# IM828XCC.net
KiCad netlist of a schematic drawn in Altium Designer
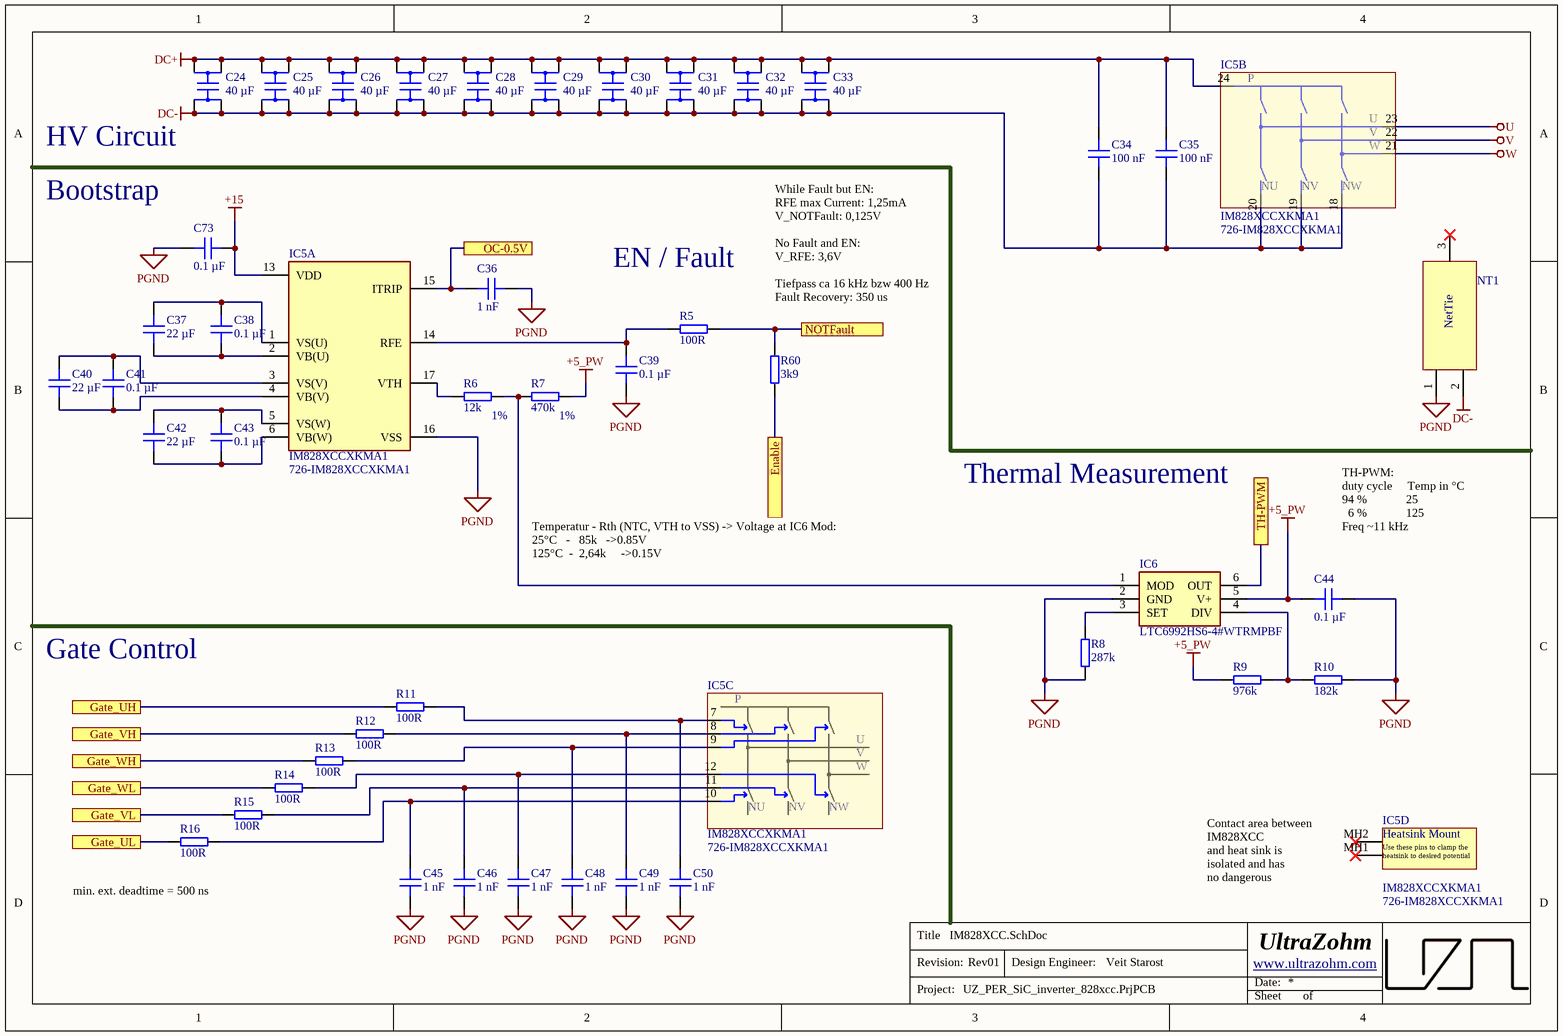
[diagram p0: IM828XCC.SchDoc]

(export (version "E")
  (design (tool "Eeschema 10.0.6"))
  (components
    (comp (ref "C24")
      (value "40 µF")
      (footprint "B32778Z")
      (description "Film Capacitors, 40 µF, 1000 VDC for DC Link")
      (fields
        (field (name "MANUFACTURER PART NUMBER") "B32778Z0406K000")
        (field (name "MANUFACTURER") "EPCOS / TDK")
        (field (name "CREATED FROM") "VStarost")
      )
      (libsource (lib "") (part "Capacitor_1"))
    )
    (comp (ref "C25")
      (value "40 µF")
      (footprint "B32778Z")
      (description "Film Capacitors, 40 µF, 1000 VDC for DC Link")
      (fields
        (field (name "MANUFACTURER PART NUMBER") "B32778Z0406K000")
        (field (name "MANUFACTURER") "EPCOS / TDK")
        (field (name "CREATED FROM") "VStarost")
      )
      (libsource (lib "") (part "Capacitor_1"))
    )
    (comp (ref "C26")
      (value "40 µF")
      (footprint "B32778Z")
      (description "Film Capacitors, 40 µF, 1000 VDC for DC Link")
      (fields
        (field (name "MANUFACTURER PART NUMBER") "B32778Z0406K000")
        (field (name "MANUFACTURER") "EPCOS / TDK")
        (field (name "CREATED FROM") "VStarost")
      )
      (libsource (lib "") (part "Capacitor_1"))
    )
    (comp (ref "C27")
      (value "40 µF")
      (footprint "B32778Z")
      (description "Film Capacitors, 40 µF, 1000 VDC for DC Link")
      (fields
        (field (name "MANUFACTURER PART NUMBER") "B32778Z0406K000")
        (field (name "MANUFACTURER") "EPCOS / TDK")
        (field (name "CREATED FROM") "VStarost")
      )
      (libsource (lib "") (part "Capacitor_1"))
    )
    (comp (ref "C28")
      (value "40 µF")
      (footprint "B32778Z")
      (description "Film Capacitors, 40 µF, 1000 VDC for DC Link")
      (fields
        (field (name "MANUFACTURER PART NUMBER") "B32778Z0406K000")
        (field (name "MANUFACTURER") "EPCOS / TDK")
        (field (name "CREATED FROM") "VStarost")
      )
      (libsource (lib "") (part "Capacitor_1"))
    )
    (comp (ref "C29")
      (value "40 µF")
      (footprint "B32778Z")
      (description "Film Capacitors, 40 µF, 1000 VDC for DC Link")
      (fields
        (field (name "MANUFACTURER PART NUMBER") "B32778Z0406K000")
        (field (name "MANUFACTURER") "EPCOS / TDK")
        (field (name "CREATED FROM") "VStarost")
      )
      (libsource (lib "") (part "Capacitor_1"))
    )
    (comp (ref "C30")
      (value "40 µF")
      (footprint "B32778Z")
      (description "Film Capacitors, 40 µF, 1000 VDC for DC Link")
      (fields
        (field (name "MANUFACTURER PART NUMBER") "B32778Z0406K000")
        (field (name "MANUFACTURER") "EPCOS / TDK")
        (field (name "CREATED FROM") "VStarost")
      )
      (libsource (lib "") (part "Capacitor_1"))
    )
    (comp (ref "C31")
      (value "40 µF")
      (footprint "B32778Z")
      (description "Film Capacitors, 40 µF, 1000 VDC for DC Link")
      (fields
        (field (name "MANUFACTURER PART NUMBER") "B32778Z0406K000")
        (field (name "MANUFACTURER") "EPCOS / TDK")
        (field (name "CREATED FROM") "VStarost")
      )
      (libsource (lib "") (part "Capacitor_1"))
    )
    (comp (ref "C32")
      (value "40 µF")
      (footprint "B32778Z")
      (description "Film Capacitors, 40 µF, 1000 VDC for DC Link")
      (fields
        (field (name "MANUFACTURER PART NUMBER") "B32778Z0406K000")
        (field (name "MANUFACTURER") "EPCOS / TDK")
        (field (name "CREATED FROM") "VStarost")
      )
      (libsource (lib "") (part "Capacitor_1"))
    )
    (comp (ref "C33")
      (value "40 µF")
      (footprint "B32778Z")
      (description "Film Capacitors, 40 µF, 1000 VDC for DC Link")
      (fields
        (field (name "MANUFACTURER PART NUMBER") "B32778Z0406K000")
        (field (name "MANUFACTURER") "EPCOS / TDK")
        (field (name "CREATED FROM") "VStarost")
      )
      (libsource (lib "") (part "Capacitor_1"))
    )
    (comp (ref "C34")
      (value "100 nF")
      (footprint "WIMA")
      (description "Folienkondensatoren 1600V .10uF 10% PCM 27.5")
      (fields
        (field (name "MANUFACTURER PART NUMBER") "MKP1T031006B00KYSD")
        (field (name "MANUFACTURER") "WIMA")
        (field (name "CREATED FROM") "VStarost")
      )
      (libsource (lib "user") (part "Capacitor"))
    )
    (comp (ref "C35")
      (value "100 nF")
      (footprint "WIMA")
      (description "Folienkondensatoren 1600V .10uF 10% PCM 27.5")
      (fields
        (field (name "MANUFACTURER PART NUMBER") "MKP1T031006B00KYSD")
        (field (name "MANUFACTURER") "WIMA")
        (field (name "CREATED FROM") "VStarost")
      )
      (libsource (lib "user") (part "Capacitor"))
    )
    (comp (ref "C36")
      (value "1 nF")
      (footprint "C_0603")
      (description "Capacitor 0603, 50 VDC, 1 nF, C0G")
      (fields
        (field (name "MANUFACTURER PART NUMBER") "06035A102JAT2A")
        (field (name "MANUFACTURER") "AVX")
        (field (name "CREATED FROM") "MGremer")
      )
      (libsource (lib "user") (part "Capacitor"))
    )
    (comp (ref "C37")
      (value "22 µF")
      (footprint "C_1206")
      (description "Capacitor 1206, 35 VDC, 22µF, X5R")
      (fields
        (field (name "MANUFACTURER PART NUMBER") "C3216X5R1V226M160AC")
        (field (name "MANUFACTURER") "TDK")
        (field (name "CREATED FROM") "VStarost")
      )
      (libsource (lib "user") (part "Capacitor"))
    )
    (comp (ref "C38")
      (value "0.1 µF")
      (footprint "C_0603")
      (description "Capacitor 0603, 50 VDC, 0.1 µF, X7R")
      (fields
        (field (name "MANUFACTURER PART NUMBER") "C0603X104K5RAC7411")
        (field (name "MANUFACTURER") "KEMET")
        (field (name "CREATED FROM") "MGremer")
      )
      (libsource (lib "user") (part "Capacitor"))
    )
    (comp (ref "C39")
      (value "0.1 µF")
      (footprint "C_0603")
      (description "Capacitor 0603, 50 VDC, 0.1 µF, X7R")
      (fields
        (field (name "MANUFACTURER PART NUMBER") "C0603X104K5RAC7411")
        (field (name "MANUFACTURER") "KEMET")
        (field (name "CREATED FROM") "MGremer")
      )
      (libsource (lib "user") (part "Capacitor"))
    )
    (comp (ref "C40")
      (value "22 µF")
      (footprint "C_1206")
      (description "Capacitor 1206, 35 VDC, 22µF, X5R")
      (fields
        (field (name "MANUFACTURER PART NUMBER") "C3216X5R1V226M160AC")
        (field (name "MANUFACTURER") "TDK")
        (field (name "CREATED FROM") "VStarost")
      )
      (libsource (lib "user") (part "Capacitor"))
    )
    (comp (ref "C41")
      (value "0.1 µF")
      (footprint "C_0603")
      (description "Capacitor 0603, 50 VDC, 0.1 µF, X7R")
      (fields
        (field (name "MANUFACTURER PART NUMBER") "C0603X104K5RAC7411")
        (field (name "MANUFACTURER") "KEMET")
        (field (name "CREATED FROM") "MGremer")
      )
      (libsource (lib "user") (part "Capacitor"))
    )
    (comp (ref "C42")
      (value "22 µF")
      (footprint "C_1206")
      (description "Capacitor 1206, 35 VDC, 22µF, X5R")
      (fields
        (field (name "MANUFACTURER PART NUMBER") "C3216X5R1V226M160AC")
        (field (name "MANUFACTURER") "TDK")
        (field (name "CREATED FROM") "VStarost")
      )
      (libsource (lib "user") (part "Capacitor"))
    )
    (comp (ref "C43")
      (value "0.1 µF")
      (footprint "C_0603")
      (description "Capacitor 0603, 50 VDC, 0.1 µF, X7R")
      (fields
        (field (name "MANUFACTURER PART NUMBER") "C0603X104K5RAC7411")
        (field (name "MANUFACTURER") "KEMET")
        (field (name "CREATED FROM") "MGremer")
      )
      (libsource (lib "user") (part "Capacitor"))
    )
    (comp (ref "C44")
      (value "0.1 µF")
      (footprint "C_0603")
      (description "Capacitor 0603, 50 VDC, 0.1 µF, X7R")
      (fields
        (field (name "MANUFACTURER PART NUMBER") "C0603X104K5RAC7411")
        (field (name "MANUFACTURER") "KEMET")
        (field (name "CREATED FROM") "MGremer")
      )
      (libsource (lib "user") (part "Capacitor"))
    )
    (comp (ref "C45")
      (value "1 nF")
      (footprint "C_0603")
      (description "Capacitor 0603, 50 VDC, 1 nF, C0G")
      (fields
        (field (name "MANUFACTURER PART NUMBER") "06035A102JAT2A")
        (field (name "MANUFACTURER") "AVX")
        (field (name "CREATED FROM") "MGremer")
      )
      (libsource (lib "user") (part "Capacitor"))
    )
    (comp (ref "C46")
      (value "1 nF")
      (footprint "C_0603")
      (description "Capacitor 0603, 50 VDC, 1 nF, C0G")
      (fields
        (field (name "MANUFACTURER PART NUMBER") "06035A102JAT2A")
        (field (name "MANUFACTURER") "AVX")
        (field (name "CREATED FROM") "MGremer")
      )
      (libsource (lib "user") (part "Capacitor"))
    )
    (comp (ref "C47")
      (value "1 nF")
      (footprint "C_0603")
      (description "Capacitor 0603, 50 VDC, 1 nF, C0G")
      (fields
        (field (name "MANUFACTURER PART NUMBER") "06035A102JAT2A")
        (field (name "MANUFACTURER") "AVX")
        (field (name "CREATED FROM") "MGremer")
      )
      (libsource (lib "user") (part "Capacitor"))
    )
    (comp (ref "C48")
      (value "1 nF")
      (footprint "C_0603")
      (description "Capacitor 0603, 50 VDC, 1 nF, C0G")
      (fields
        (field (name "MANUFACTURER PART NUMBER") "06035A102JAT2A")
        (field (name "MANUFACTURER") "AVX")
        (field (name "CREATED FROM") "MGremer")
      )
      (libsource (lib "user") (part "Capacitor"))
    )
    (comp (ref "C49")
      (value "1 nF")
      (footprint "C_0603")
      (description "Capacitor 0603, 50 VDC, 1 nF, C0G")
      (fields
        (field (name "MANUFACTURER PART NUMBER") "06035A102JAT2A")
        (field (name "MANUFACTURER") "AVX")
        (field (name "CREATED FROM") "MGremer")
      )
      (libsource (lib "user") (part "Capacitor"))
    )
    (comp (ref "C50")
      (value "1 nF")
      (footprint "C_0603")
      (description "Capacitor 0603, 50 VDC, 1 nF, C0G")
      (fields
        (field (name "MANUFACTURER PART NUMBER") "06035A102JAT2A")
        (field (name "MANUFACTURER") "AVX")
        (field (name "CREATED FROM") "MGremer")
      )
      (libsource (lib "user") (part "Capacitor"))
    )
    (comp (ref "C73")
      (value "0.1 µF")
      (footprint "C_0603")
      (description "Capacitor 0603, 50 VDC, 0.1 µF, X7R")
      (fields
        (field (name "MANUFACTURER PART NUMBER") "C0603X104K5RAC7411")
        (field (name "MANUFACTURER") "KEMET")
        (field (name "CREATED FROM") "MGremer")
      )
      (libsource (lib "user") (part "Capacitor"))
    )
    (comp (ref "IC5")
      (value "IM828XCCXKMA1")
      (footprint "IM828XCCXKMA1")
      (description "Motor/Motion/Ignition Controllers & Drivers SiC MOSFET")
      (fields
        (field (name "MOUSER PART NUMBER") "726-IM828XCCXKMA1")
        (field (name "SUPPLIER PART NUMBER 1") "726-IM828XCCXKMA1")
        (field (name "MANUFACTURER") "Infineon")
        (field (name "CREATED FROM") "VStarost")
      )
      (libsource (lib "user") (part "IM828XCCXKMA1"))
    )
    (comp (ref "IC6")
      (value "LTC6992HS6-4#WTRMPBF")
      (footprint "SOT95P280X100-6N")
      (description "Switching Controllers PWM with 5% to 100% Pulse Width Control")
      (fields (field (name "MANUFACTURER") "Analog Devices") (field (name "CREATED FROM") "DHufnagel"))
      (libsource (lib "user") (part "LTC6992HS6-4#WTRMPBF"))
    )
    (comp (ref "NT1")
      (value "Net Tie 2 to 1")
      (footprint "2_to_1_NetTie_1mm")
      (description "Net Tie 2 to 1. Joints two nets without producing a DRC error")
      (fields (field (name "CREATED BY") "T. Wendt"))
      (libsource (lib "user") (part "NetTie_2_to_1"))
    )
    (comp (ref "R5")
      (value "100R")
      (footprint "RES 0603_1608")
      (description "SMD resistor E24 series")
      (fields
        (field (name "MANUFACTURER PART NUMBER") "RK73B1JTTD101J")
        (field (name "MANUFACTURER") "KOA Speer")
        (field (name "CREATED FROM") "MGremer")
      )
      (libsource (lib "user") (part "Resistor"))
    )
    (comp (ref "R6")
      (value "12k")
      (footprint "RES 0603_1608")
      (description "SMD resistor E24 series 12 kOhms 100mW 0603 1%")
      (fields
        (field (name "MANUFACTURER PART NUMBER") "AC0603FR-1012KL")
        (field (name "MANUFACTURER") "YAGEO")
        (field (name "TOLERANCE") "1%")
        (field (name "CREATED FROM") "VStarost")
      )
      (libsource (lib "user") (part "Resistor"))
    )
    (comp (ref "R7")
      (value "470k")
      (footprint "RES 0603_1608")
      (description "SMD resistor E24 series 470 kOhms 100-200 mW 0603 1%")
      (fields
        (field (name "MANUFACTURER PART NUMBER") "RC0603FR-10470KL")
        (field (name "MANUFACTURER") "YAGEO")
        (field (name "TOLERANCE") "1%")
        (field (name "CREATED FROM") "VStarost")
      )
      (libsource (lib "user") (part "Resistor"))
    )
    (comp (ref "R8")
      (value "287k")
      (footprint "RES 0805_2012")
      (description "SMD resistor 1%")
      (fields
        (field (name "MANUFACTURER PART NUMBER") "ERJ-6ENF2873V")
        (field (name "MANUFACTURER") "Panasonic")
        (field (name "CREATED FROM") "MGremer")
      )
      (libsource (lib "user") (part "Resistor"))
    )
    (comp (ref "R9")
      (value "976k")
      (footprint "RES 0603_1608")
      (description "SMD resistor 1%, 50V, 100ppm")
      (fields
        (field (name "MANUFACTURER PART NUMBER") "CR0603-FX-9763ELF")
        (field (name "MANUFACTURER") "Bourns")
        (field (name "CREATED FROM") "DHufnagel")
      )
      (libsource (lib "user") (part "Resistor"))
    )
    (comp (ref "R10")
      (value "182k")
      (footprint "RES 0603_1608")
      (description "SMD resistor 1%, 50V, 100ppm")
      (fields
        (field (name "MANUFACTURER PART NUMBER") "CR0603-FX-1823ELF")
        (field (name "MANUFACTURER") "Bourns")
        (field (name "CREATED FROM") "DHufnagel")
      )
      (libsource (lib "user") (part "Resistor"))
    )
    (comp (ref "R11")
      (value "100R")
      (footprint "RES 0603_1608")
      (description "SMD resistor E24 series")
      (fields
        (field (name "MANUFACTURER PART NUMBER") "RK73B1JTTD101J")
        (field (name "MANUFACTURER") "KOA Speer")
        (field (name "CREATED FROM") "MGremer")
      )
      (libsource (lib "user") (part "Resistor"))
    )
    (comp (ref "R12")
      (value "100R")
      (footprint "RES 0603_1608")
      (description "SMD resistor E24 series")
      (fields
        (field (name "MANUFACTURER PART NUMBER") "RK73B1JTTD101J")
        (field (name "MANUFACTURER") "KOA Speer")
        (field (name "CREATED FROM") "MGremer")
      )
      (libsource (lib "user") (part "Resistor"))
    )
    (comp (ref "R13")
      (value "100R")
      (footprint "RES 0603_1608")
      (description "SMD resistor E24 series")
      (fields
        (field (name "MANUFACTURER PART NUMBER") "RK73B1JTTD101J")
        (field (name "MANUFACTURER") "KOA Speer")
        (field (name "CREATED FROM") "MGremer")
      )
      (libsource (lib "user") (part "Resistor"))
    )
    (comp (ref "R14")
      (value "100R")
      (footprint "RES 0603_1608")
      (description "SMD resistor E24 series")
      (fields
        (field (name "MANUFACTURER PART NUMBER") "RK73B1JTTD101J")
        (field (name "MANUFACTURER") "KOA Speer")
        (field (name "CREATED FROM") "MGremer")
      )
      (libsource (lib "user") (part "Resistor"))
    )
    (comp (ref "R15")
      (value "100R")
      (footprint "RES 0603_1608")
      (description "SMD resistor E24 series")
      (fields
        (field (name "MANUFACTURER PART NUMBER") "RK73B1JTTD101J")
        (field (name "MANUFACTURER") "KOA Speer")
        (field (name "CREATED FROM") "MGremer")
      )
      (libsource (lib "user") (part "Resistor"))
    )
    (comp (ref "R16")
      (value "100R")
      (footprint "RES 0603_1608")
      (description "SMD resistor E24 series")
      (fields
        (field (name "MANUFACTURER PART NUMBER") "RK73B1JTTD101J")
        (field (name "MANUFACTURER") "KOA Speer")
        (field (name "CREATED FROM") "MGremer")
      )
      (libsource (lib "user") (part "Resistor"))
    )
    (comp (ref "R60")
      (value "3k9")
      (footprint "RES 0603_1608")
      (description "SMD resistor E24 series")
      (fields
        (field (name "MANUFACTURER PART NUMBER") "RK73B1JTTDD392J")
        (field (name "MANUFACTURER") "KOA Speer")
        (field (name "CREATED FROM") "MGremer")
      )
      (libsource (lib "user") (part "Resistor"))
    )
  )
  (nets
    (net (code "1") (name "+5_PW") (class "Default")
      (node (ref "C44") (pin "2") (pinfunction "2_2") (pintype "passive"))
      (node (ref "IC6") (pin "5") (pinfunction "V+_5") (pintype "passive"))
      (node (ref "R7") (pin "2") (pinfunction "2_2") (pintype "passive"))
      (node (ref "R9") (pin "1") (pinfunction "1_1") (pintype "passive"))
    )
    (net (code "2") (name "+15") (class "Default")
      (node (ref "C73") (pin "1") (pinfunction "1_1") (pintype "passive"))
      (node (ref "IC5") (pin "13") (pinfunction "VDD_13") (pintype "passive"))
    )
    (net (code "3") (name "/Enable") (class "Default")
      (node (ref "R60") (pin "1") (pinfunction "1_1") (pintype "passive"))
    )
    (net (code "4") (name "/Gate_UH") (class "Default")
      (node (ref "R11") (pin "1") (pinfunction "1_1") (pintype "passive"))
    )
    (net (code "5") (name "/Gate_UL") (class "Default")
      (node (ref "R16") (pin "1") (pinfunction "1_1") (pintype "passive"))
    )
    (net (code "6") (name "/Gate_VH") (class "Default")
      (node (ref "R12") (pin "1") (pinfunction "1_1") (pintype "passive"))
    )
    (net (code "7") (name "/Gate_VL") (class "Default")
      (node (ref "R15") (pin "1") (pinfunction "1_1") (pintype "passive"))
    )
    (net (code "8") (name "/Gate_WH") (class "Default")
      (node (ref "R13") (pin "1") (pinfunction "1_1") (pintype "passive"))
    )
    (net (code "9") (name "/Gate_WL") (class "Default")
      (node (ref "R14") (pin "1") (pinfunction "1_1") (pintype "passive"))
    )
    (net (code "10") (name "/NOTFault") (class "Default")
      (node (ref "R5") (pin "2") (pinfunction "2_2") (pintype "passive"))
      (node (ref "R60") (pin "2") (pinfunction "2_2") (pintype "passive"))
    )
    (net (code "11") (name "/OC-0.5V") (class "Default")
      (node (ref "C36") (pin "2") (pinfunction "2_2") (pintype "passive"))
      (node (ref "IC5") (pin "15") (pinfunction "ITRIP_15") (pintype "passive"))
    )
    (net (code "12") (name "/TH-PWM") (class "Default")
      (node (ref "IC6") (pin "6") (pinfunction "OUT_6") (pintype "passive"))
    )
    (net (code "13") (name "DC+") (class "Default")
      (node (ref "C24") (pin "2") (pinfunction "2_2") (pintype "passive"))
      (node (ref "C24") (pin "3") (pinfunction "3_3") (pintype "passive"))
      (node (ref "C25") (pin "2") (pinfunction "2_2") (pintype "passive"))
      (node (ref "C25") (pin "3") (pinfunction "3_3") (pintype "passive"))
      (node (ref "C26") (pin "2") (pinfunction "2_2") (pintype "passive"))
      (node (ref "C26") (pin "3") (pinfunction "3_3") (pintype "passive"))
      (node (ref "C27") (pin "2") (pinfunction "2_2") (pintype "passive"))
      (node (ref "C27") (pin "3") (pinfunction "3_3") (pintype "passive"))
      (node (ref "C28") (pin "2") (pinfunction "2_2") (pintype "passive"))
      (node (ref "C28") (pin "3") (pinfunction "3_3") (pintype "passive"))
      (node (ref "C29") (pin "2") (pinfunction "2_2") (pintype "passive"))
      (node (ref "C29") (pin "3") (pinfunction "3_3") (pintype "passive"))
      (node (ref "C30") (pin "2") (pinfunction "2_2") (pintype "passive"))
      (node (ref "C30") (pin "3") (pinfunction "3_3") (pintype "passive"))
      (node (ref "C31") (pin "2") (pinfunction "2_2") (pintype "passive"))
      (node (ref "C31") (pin "3") (pinfunction "3_3") (pintype "passive"))
      (node (ref "C32") (pin "2") (pinfunction "2_2") (pintype "passive"))
      (node (ref "C32") (pin "3") (pinfunction "3_3") (pintype "passive"))
      (node (ref "C33") (pin "2") (pinfunction "2_2") (pintype "passive"))
      (node (ref "C33") (pin "3") (pinfunction "3_3") (pintype "passive"))
      (node (ref "C34") (pin "2") (pinfunction "2_2") (pintype "passive"))
      (node (ref "C35") (pin "2") (pinfunction "2_2") (pintype "passive"))
      (node (ref "IC5") (pin "24") (pinfunction "P_24") (pintype "passive"))
    )
    (net (code "14") (name "DC-") (class "Default")
      (node (ref "C24") (pin "1") (pinfunction "1_1") (pintype "passive"))
      (node (ref "C24") (pin "4") (pinfunction "4_4") (pintype "passive"))
      (node (ref "C25") (pin "1") (pinfunction "1_1") (pintype "passive"))
      (node (ref "C25") (pin "4") (pinfunction "4_4") (pintype "passive"))
      (node (ref "C26") (pin "1") (pinfunction "1_1") (pintype "passive"))
      (node (ref "C26") (pin "4") (pinfunction "4_4") (pintype "passive"))
      (node (ref "C27") (pin "1") (pinfunction "1_1") (pintype "passive"))
      (node (ref "C27") (pin "4") (pinfunction "4_4") (pintype "passive"))
      (node (ref "C28") (pin "1") (pinfunction "1_1") (pintype "passive"))
      (node (ref "C28") (pin "4") (pinfunction "4_4") (pintype "passive"))
      (node (ref "C29") (pin "1") (pinfunction "1_1") (pintype "passive"))
      (node (ref "C29") (pin "4") (pinfunction "4_4") (pintype "passive"))
      (node (ref "C30") (pin "1") (pinfunction "1_1") (pintype "passive"))
      (node (ref "C30") (pin "4") (pinfunction "4_4") (pintype "passive"))
      (node (ref "C31") (pin "1") (pinfunction "1_1") (pintype "passive"))
      (node (ref "C31") (pin "4") (pinfunction "4_4") (pintype "passive"))
      (node (ref "C32") (pin "1") (pinfunction "1_1") (pintype "passive"))
      (node (ref "C32") (pin "4") (pinfunction "4_4") (pintype "passive"))
      (node (ref "C33") (pin "1") (pinfunction "1_1") (pintype "passive"))
      (node (ref "C33") (pin "4") (pinfunction "4_4") (pintype "passive"))
      (node (ref "C34") (pin "1") (pinfunction "1_1") (pintype "passive"))
      (node (ref "C35") (pin "1") (pinfunction "1_1") (pintype "passive"))
      (node (ref "IC5") (pin "18") (pinfunction "NW_18") (pintype "passive"))
      (node (ref "IC5") (pin "19") (pinfunction "NV_19") (pintype "passive"))
      (node (ref "IC5") (pin "20") (pinfunction "NU_20") (pintype "passive"))
      (node (ref "NT1") (pin "2") (pinfunction "2_2") (pintype "passive"))
    )
    (net (code "15") (name "Net-(IC5A-RFE)") (class "Default")
      (node (ref "C39") (pin "2") (pinfunction "2_2") (pintype "passive"))
      (node (ref "IC5") (pin "14") (pinfunction "RFE_14") (pintype "passive"))
      (node (ref "R5") (pin "1") (pinfunction "1_1") (pintype "passive"))
    )
    (net (code "16") (name "Net-(IC5A-VB(U))") (class "Default")
      (node (ref "C37") (pin "1") (pinfunction "1_1") (pintype "passive"))
      (node (ref "C38") (pin "1") (pinfunction "1_1") (pintype "passive"))
      (node (ref "IC5") (pin "2") (pinfunction "VB(U)_2") (pintype "passive"))
    )
    (net (code "17") (name "Net-(IC5A-VB(V))") (class "Default")
      (node (ref "C40") (pin "1") (pinfunction "1_1") (pintype "passive"))
      (node (ref "C41") (pin "1") (pinfunction "1_1") (pintype "passive"))
      (node (ref "IC5") (pin "4") (pinfunction "VB(V)_4") (pintype "passive"))
    )
    (net (code "18") (name "Net-(IC5A-VB(W))") (class "Default")
      (node (ref "C42") (pin "1") (pinfunction "1_1") (pintype "passive"))
      (node (ref "C43") (pin "1") (pinfunction "1_1") (pintype "passive"))
      (node (ref "IC5") (pin "6") (pinfunction "VB(W)_6") (pintype "passive"))
    )
    (net (code "19") (name "Net-(IC5A-VS(U))") (class "Default")
      (node (ref "C37") (pin "2") (pinfunction "2_2") (pintype "passive"))
      (node (ref "C38") (pin "2") (pinfunction "2_2") (pintype "passive"))
      (node (ref "IC5") (pin "1") (pinfunction "VS(U)_1") (pintype "passive"))
    )
    (net (code "20") (name "Net-(IC5A-VS(V))") (class "Default")
      (node (ref "C40") (pin "2") (pinfunction "2_2") (pintype "passive"))
      (node (ref "C41") (pin "2") (pinfunction "2_2") (pintype "passive"))
      (node (ref "IC5") (pin "3") (pinfunction "VS(V)_3") (pintype "passive"))
    )
    (net (code "21") (name "Net-(IC5A-VS(W))") (class "Default")
      (node (ref "C42") (pin "2") (pinfunction "2_2") (pintype "passive"))
      (node (ref "C43") (pin "2") (pinfunction "2_2") (pintype "passive"))
      (node (ref "IC5") (pin "5") (pinfunction "VS(W)_5") (pintype "passive"))
    )
    (net (code "22") (name "Net-(IC5A-VTH)") (class "Default")
      (node (ref "IC5") (pin "17") (pinfunction "VTH_17") (pintype "passive"))
      (node (ref "R6") (pin "1") (pinfunction "1_1") (pintype "passive"))
    )
    (net (code "23") (name "Net-(IC5C-HIN(U))") (class "Default")
      (node (ref "C50") (pin "2") (pinfunction "2_2") (pintype "passive"))
      (node (ref "IC5") (pin "7") (pinfunction "HIN(U)_7") (pintype "passive"))
      (node (ref "R11") (pin "2") (pinfunction "2_2") (pintype "passive"))
    )
    (net (code "24") (name "Net-(IC5C-HIN(V))") (class "Default")
      (node (ref "C49") (pin "2") (pinfunction "2_2") (pintype "passive"))
      (node (ref "IC5") (pin "8") (pinfunction "HIN(V)_8") (pintype "passive"))
      (node (ref "R12") (pin "2") (pinfunction "2_2") (pintype "passive"))
    )
    (net (code "25") (name "Net-(IC5C-HIN(W))") (class "Default")
      (node (ref "C48") (pin "2") (pinfunction "2_2") (pintype "passive"))
      (node (ref "IC5") (pin "9") (pinfunction "HIN(W)_9") (pintype "passive"))
      (node (ref "R13") (pin "2") (pinfunction "2_2") (pintype "passive"))
    )
    (net (code "26") (name "Net-(IC5C-LIN(U))") (class "Default")
      (node (ref "C45") (pin "2") (pinfunction "2_2") (pintype "passive"))
      (node (ref "IC5") (pin "10") (pinfunction "LIN(U)_10") (pintype "passive"))
      (node (ref "R16") (pin "2") (pinfunction "2_2") (pintype "passive"))
    )
    (net (code "27") (name "Net-(IC5C-LIN(V))") (class "Default")
      (node (ref "C46") (pin "2") (pinfunction "2_2") (pintype "passive"))
      (node (ref "IC5") (pin "11") (pinfunction "LIN(V)_11") (pintype "passive"))
      (node (ref "R15") (pin "2") (pinfunction "2_2") (pintype "passive"))
    )
    (net (code "28") (name "Net-(IC5C-LIN(W))") (class "Default")
      (node (ref "C47") (pin "2") (pinfunction "2_2") (pintype "passive"))
      (node (ref "IC5") (pin "12") (pinfunction "LIN(W)_12") (pintype "passive"))
      (node (ref "R14") (pin "2") (pinfunction "2_2") (pintype "passive"))
    )
    (net (code "29") (name "Net-(IC6-DIV)") (class "Default")
      (node (ref "IC6") (pin "4") (pinfunction "DIV_4") (pintype "passive"))
      (node (ref "R10") (pin "1") (pinfunction "1_1") (pintype "passive"))
      (node (ref "R9") (pin "2") (pinfunction "2_2") (pintype "passive"))
    )
    (net (code "30") (name "Net-(IC6-MOD)") (class "Default")
      (node (ref "IC6") (pin "1") (pinfunction "MOD_1") (pintype "passive"))
      (node (ref "R6") (pin "2") (pinfunction "2_2") (pintype "passive"))
      (node (ref "R7") (pin "1") (pinfunction "1_1") (pintype "passive"))
    )
    (net (code "31") (name "Net-(IC6-SET)") (class "Default")
      (node (ref "IC6") (pin "3") (pinfunction "SET_3") (pintype "passive"))
      (node (ref "R8") (pin "2") (pinfunction "2_2") (pintype "passive"))
    )
    (net (code "32") (name "PGND") (class "Default")
      (node (ref "C36") (pin "1") (pinfunction "1_1") (pintype "passive"))
      (node (ref "C39") (pin "1") (pinfunction "1_1") (pintype "passive"))
      (node (ref "C44") (pin "1") (pinfunction "1_1") (pintype "passive"))
      (node (ref "C45") (pin "1") (pinfunction "1_1") (pintype "passive"))
      (node (ref "C46") (pin "1") (pinfunction "1_1") (pintype "passive"))
      (node (ref "C47") (pin "1") (pinfunction "1_1") (pintype "passive"))
      (node (ref "C48") (pin "1") (pinfunction "1_1") (pintype "passive"))
      (node (ref "C49") (pin "1") (pinfunction "1_1") (pintype "passive"))
      (node (ref "C50") (pin "1") (pinfunction "1_1") (pintype "passive"))
      (node (ref "C73") (pin "2") (pinfunction "2_2") (pintype "passive"))
      (node (ref "IC5") (pin "16") (pinfunction "VSS_16") (pintype "passive"))
      (node (ref "IC6") (pin "2") (pinfunction "GND_2") (pintype "passive"))
      (node (ref "NT1") (pin "1") (pinfunction "1_1") (pintype "passive"))
      (node (ref "R10") (pin "2") (pinfunction "2_2") (pintype "passive"))
      (node (ref "R8") (pin "1") (pinfunction "1_1") (pintype "passive"))
    )
    (net (code "33") (name "U") (class "Default")
      (node (ref "IC5") (pin "23") (pinfunction "U_23") (pintype "passive"))
    )
    (net (code "34") (name "V") (class "Default")
      (node (ref "IC5") (pin "22") (pinfunction "V_22") (pintype "passive"))
    )
    (net (code "35") (name "W") (class "Default")
      (node (ref "IC5") (pin "21") (pinfunction "W_21") (pintype "passive"))
    )
    (net (code "36") (name "unconnected-(IC5D-HeatsinkScrew-PadMH1)") (class "Default")
      (node (ref "IC5") (pin "MH1") (pinfunction "HeatsinkScrew_MH1") (pintype "passive+no_connect"))
    )
    (net (code "37") (name "unconnected-(IC5D-HeatsinkScrew2-PadMH2)") (class "Default")
      (node (ref "IC5") (pin "MH2") (pinfunction "HeatsinkScrew2_MH2") (pintype "passive+no_connect"))
    )
    (net (code "38") (name "unconnected-(NT1-Pad3)") (class "Default")
      (node (ref "NT1") (pin "3") (pinfunction "3_3") (pintype "passive+no_connect"))
    )
  )
)
